# Sheet1.net
KiCad netlist of a schematic drawn in Altium Designer
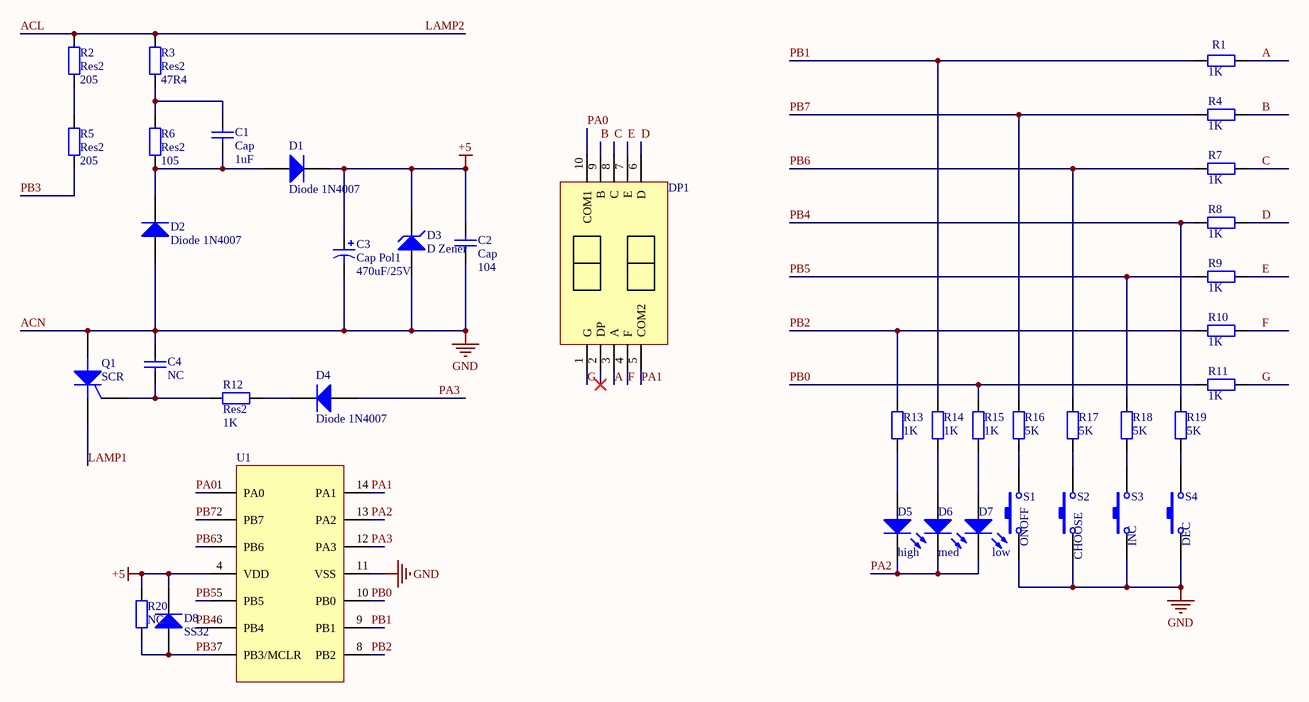
[diagram p0: Sheet1.SchDoc]

(export (version "E")
  (design (tool "Eeschema 10.0.6"))
  (components
    (comp (ref "C1")
      (value "Cap")
      (footprint "RAD-0.3")
      (description "Capacitor")
      (fields (field (name "ALTIUM_VALUE") "1uF") (field (name "PUBLISHER") "Altium Limited"))
      (libsource (lib "Miscellaneous Devices") (part "Cap"))
    )
    (comp (ref "C2")
      (value "Cap")
      (footprint "RAD-0.3")
      (description "Capacitor")
      (fields (field (name "ALTIUM_VALUE") "104") (field (name "PUBLISHER") "Altium Limited"))
      (libsource (lib "Miscellaneous Devices") (part "Cap"))
    )
    (comp (ref "C3")
      (value "Cap Pol1")
      (footprint "RB7.6-15")
      (description "Polarized Capacitor (Radial)")
      (fields (field (name "ALTIUM_VALUE") "470uF/25V") (field (name "PUBLISHER") "Altium Limited"))
      (libsource (lib "Miscellaneous Devices") (part "Cap Pol1"))
    )
    (comp (ref "C4")
      (value "NC")
      (footprint "RAD-0.3")
      (description "Capacitor")
      (fields (field (name "PUBLISHER") "Altium Limited"))
      (libsource (lib "Miscellaneous Devices") (part "Cap"))
    )
    (comp (ref "D1")
      (value "Diode 1N4007")
      (footprint "DO-41")
      (description "1 Amp General Purpose Rectifier")
      (fields (field (name "PUBLISHER") "Altium Limited"))
      (libsource (lib "Miscellaneous Devices") (part "Diode 1N4007"))
    )
    (comp (ref "D2")
      (value "Diode 1N4007")
      (footprint "DO-41")
      (description "1 Amp General Purpose Rectifier")
      (fields (field (name "PUBLISHER") "Altium Limited"))
      (libsource (lib "Miscellaneous Devices") (part "Diode 1N4007"))
    )
    (comp (ref "D3")
      (value "D Zener")
      (footprint "DIODE-0.7")
      (description "Zener Diode")
      (fields (field (name "PUBLISHER") "Altium Limited"))
      (libsource (lib "Miscellaneous Devices") (part "D Zener"))
    )
    (comp (ref "D4")
      (value "Diode 1N4007")
      (footprint "DO-41")
      (description "1 Amp General Purpose Rectifier")
      (fields (field (name "PUBLISHER") "Altium Limited"))
      (libsource (lib "Miscellaneous Devices") (part "Diode 1N4007"))
    )
    (comp (ref "D5")
      (value "high")
      (footprint "LED-0")
      (description "Typical INFRARED GaAs LED")
      (fields (field (name "PUBLISHER") "Altium Limited"))
      (libsource (lib "Miscellaneous Devices") (part "LED0"))
    )
    (comp (ref "D6")
      (value "med")
      (footprint "LED-0")
      (description "Typical INFRARED GaAs LED")
      (fields (field (name "PUBLISHER") "Altium Limited"))
      (libsource (lib "Miscellaneous Devices") (part "LED0"))
    )
    (comp (ref "D7")
      (value "low")
      (footprint "LED-0")
      (description "Typical INFRARED GaAs LED")
      (fields (field (name "PUBLISHER") "Altium Limited"))
      (libsource (lib "Miscellaneous Devices") (part "LED0"))
    )
    (comp (ref "D8")
      (value "SS32")
      (footprint "DO-41")
      (description "1 Amp General Purpose Rectifier")
      (fields (field (name "PUBLISHER") "Altium Limited"))
      (libsource (lib "Miscellaneous Devices") (part "Diode 1N4007"))
    )
    (comp (ref "DP1") (value "~") (libsource (lib "MyLib") (part "gongyinshumaguan*2")))
    (comp (ref "Q1")
      (value "SCR")
      (footprint "TO-220-AB")
      (description "Silicon Controlled Rectifier")
      (fields (field (name "PUBLISHER") "Altium Limited"))
      (libsource (lib "Miscellaneous Devices") (part "SCR"))
    )
    (comp (ref "R1")
      (value "1K")
      (footprint "AXIAL-0.4")
      (description "Resistor")
      (fields (field (name "Comment") "Res2") (field (name "PUBLISHER") "Altium Limited"))
      (libsource (lib "") (part "Res2_1"))
    )
    (comp (ref "R2")
      (value "Res2")
      (footprint "AXIAL-0.4")
      (description "Resistor")
      (fields (field (name "ALTIUM_VALUE") "205") (field (name "PUBLISHER") "Altium Limited"))
      (libsource (lib "Miscellaneous Devices") (part "Res2"))
    )
    (comp (ref "R3")
      (value "Res2")
      (footprint "AXIAL-0.4")
      (description "Resistor")
      (fields (field (name "ALTIUM_VALUE") "47R4") (field (name "PUBLISHER") "Altium Limited"))
      (libsource (lib "Miscellaneous Devices") (part "Res2"))
    )
    (comp (ref "R4")
      (value "1K")
      (footprint "AXIAL-0.4")
      (description "Resistor")
      (fields (field (name "Comment") "Res2") (field (name "PUBLISHER") "Altium Limited"))
      (libsource (lib "") (part "Res2_1"))
    )
    (comp (ref "R5")
      (value "Res2")
      (footprint "AXIAL-0.4")
      (description "Resistor")
      (fields (field (name "ALTIUM_VALUE") "205") (field (name "PUBLISHER") "Altium Limited"))
      (libsource (lib "Miscellaneous Devices") (part "Res2"))
    )
    (comp (ref "R6")
      (value "Res2")
      (footprint "AXIAL-0.4")
      (description "Resistor")
      (fields (field (name "ALTIUM_VALUE") "105") (field (name "PUBLISHER") "Altium Limited"))
      (libsource (lib "Miscellaneous Devices") (part "Res2"))
    )
    (comp (ref "R7")
      (value "1K")
      (footprint "AXIAL-0.4")
      (description "Resistor")
      (fields (field (name "Comment") "Res2") (field (name "PUBLISHER") "Altium Limited"))
      (libsource (lib "") (part "Res2_1"))
    )
    (comp (ref "R8")
      (value "1K")
      (footprint "AXIAL-0.4")
      (description "Resistor")
      (fields (field (name "Comment") "Res2") (field (name "PUBLISHER") "Altium Limited"))
      (libsource (lib "") (part "Res2_1"))
    )
    (comp (ref "R9")
      (value "1K")
      (footprint "AXIAL-0.4")
      (description "Resistor")
      (fields (field (name "Comment") "Res2") (field (name "PUBLISHER") "Altium Limited"))
      (libsource (lib "") (part "Res2_1"))
    )
    (comp (ref "R10")
      (value "1K")
      (footprint "AXIAL-0.4")
      (description "Resistor")
      (fields (field (name "Comment") "Res2") (field (name "PUBLISHER") "Altium Limited"))
      (libsource (lib "") (part "Res2_1"))
    )
    (comp (ref "R11")
      (value "1K")
      (footprint "AXIAL-0.4")
      (description "Resistor")
      (fields (field (name "Comment") "Res2") (field (name "PUBLISHER") "Altium Limited"))
      (libsource (lib "") (part "Res2_1"))
    )
    (comp (ref "R12")
      (value "Res2")
      (footprint "AXIAL-0.4")
      (description "Resistor")
      (fields (field (name "ALTIUM_VALUE") "1K") (field (name "PUBLISHER") "Altium Limited"))
      (libsource (lib "") (part "Res2_2"))
    )
    (comp (ref "R13")
      (value "1K")
      (footprint "AXIAL-0.4")
      (description "Resistor")
      (fields (field (name "Comment") "Res2") (field (name "PUBLISHER") "Altium Limited"))
      (libsource (lib "Miscellaneous Devices") (part "Res2"))
    )
    (comp (ref "R14")
      (value "1K")
      (footprint "AXIAL-0.4")
      (description "Resistor")
      (fields (field (name "Comment") "Res2") (field (name "PUBLISHER") "Altium Limited"))
      (libsource (lib "Miscellaneous Devices") (part "Res2"))
    )
    (comp (ref "R15")
      (value "1K")
      (footprint "AXIAL-0.4")
      (description "Resistor")
      (fields (field (name "Comment") "Res2") (field (name "PUBLISHER") "Altium Limited"))
      (libsource (lib "Miscellaneous Devices") (part "Res2"))
    )
    (comp (ref "R16")
      (value "5K")
      (footprint "AXIAL-0.4")
      (description "Resistor")
      (fields (field (name "Comment") "Res2") (field (name "PUBLISHER") "Altium Limited"))
      (libsource (lib "Miscellaneous Devices") (part "Res2"))
    )
    (comp (ref "R17")
      (value "5K")
      (footprint "AXIAL-0.4")
      (description "Resistor")
      (fields (field (name "Comment") "Res2") (field (name "PUBLISHER") "Altium Limited"))
      (libsource (lib "Miscellaneous Devices") (part "Res2"))
    )
    (comp (ref "R18")
      (value "5K")
      (footprint "AXIAL-0.4")
      (description "Resistor")
      (fields (field (name "Comment") "Res2") (field (name "PUBLISHER") "Altium Limited"))
      (libsource (lib "Miscellaneous Devices") (part "Res2"))
    )
    (comp (ref "R19")
      (value "5K")
      (footprint "AXIAL-0.4")
      (description "Resistor")
      (fields (field (name "Comment") "Res2") (field (name "PUBLISHER") "Altium Limited"))
      (libsource (lib "Miscellaneous Devices") (part "Res2"))
    )
    (comp (ref "R20")
      (value "NC")
      (footprint "AXIAL-0.4")
      (description "Resistor")
      (fields (field (name "Comment") "Res2") (field (name "PUBLISHER") "Altium Limited"))
      (libsource (lib "Miscellaneous Devices") (part "Res2"))
    )
    (comp (ref "S1")
      (value "ONOFF")
      (footprint "SPST-2")
      (description "Switch")
      (fields (field (name "PUBLISHER") "Altium Limited"))
      (libsource (lib "Miscellaneous Devices") (part "SW-PB"))
    )
    (comp (ref "S2")
      (value "CHOOSE")
      (footprint "SPST-2")
      (description "Switch")
      (fields (field (name "PUBLISHER") "Altium Limited"))
      (libsource (lib "Miscellaneous Devices") (part "SW-PB"))
    )
    (comp (ref "S3")
      (value "INC")
      (footprint "SPST-2")
      (description "Switch")
      (fields (field (name "PUBLISHER") "Altium Limited"))
      (libsource (lib "Miscellaneous Devices") (part "SW-PB"))
    )
    (comp (ref "S4")
      (value "DEC")
      (footprint "SPST-2")
      (description "Switch")
      (fields (field (name "PUBLISHER") "Altium Limited"))
      (libsource (lib "Miscellaneous Devices") (part "SW-PB"))
    )
    (comp (ref "U1") (value "SQ013-SOP14") (libsource (lib "MyLib") (part "SQ013-SOP14")))
  )
  (nets
    (net (code "1") (name "+5") (class "Default")
      (node (ref "C2") (pin "2") (pinfunction "2_2") (pintype "passive"))
      (node (ref "C3") (pin "1") (pinfunction "1_1") (pintype "passive"))
      (node (ref "D1") (pin "2") (pinfunction "K_2") (pintype "passive"))
      (node (ref "D3") (pin "2") (pinfunction "K_2") (pintype "passive"))
      (node (ref "D8") (pin "2") (pinfunction "K_2") (pintype "passive"))
      (node (ref "R20") (pin "2") (pinfunction "2_2") (pintype "passive"))
      (node (ref "U1") (pin "4") (pinfunction "VDD_4") (pintype "passive"))
    )
    (net (code "2") (name "/A") (class "Default")
      (node (ref "DP1") (pin "3") (pinfunction "A_3") (pintype "passive"))
      (node (ref "R1") (pin "2") (pinfunction "2_2") (pintype "passive"))
    )
    (net (code "3") (name "/ACL") (class "Default")
      (node (ref "R2") (pin "2") (pinfunction "2_2") (pintype "passive"))
      (node (ref "R3") (pin "2") (pinfunction "2_2") (pintype "passive"))
    )
    (net (code "4") (name "/B") (class "Default")
      (node (ref "DP1") (pin "9") (pinfunction "B_9") (pintype "passive"))
      (node (ref "R4") (pin "2") (pinfunction "2_2") (pintype "passive"))
    )
    (net (code "5") (name "/C") (class "Default")
      (node (ref "DP1") (pin "8") (pinfunction "C_8") (pintype "passive"))
      (node (ref "R7") (pin "2") (pinfunction "2_2") (pintype "passive"))
    )
    (net (code "6") (name "/D") (class "Default")
      (node (ref "DP1") (pin "6") (pinfunction "D_6") (pintype "passive"))
      (node (ref "R8") (pin "2") (pinfunction "2_2") (pintype "passive"))
    )
    (net (code "7") (name "/E") (class "Default")
      (node (ref "DP1") (pin "7") (pinfunction "E_7") (pintype "passive"))
      (node (ref "R9") (pin "2") (pinfunction "2_2") (pintype "passive"))
    )
    (net (code "8") (name "/F") (class "Default")
      (node (ref "DP1") (pin "4") (pinfunction "F_4") (pintype "passive"))
      (node (ref "R10") (pin "2") (pinfunction "2_2") (pintype "passive"))
    )
    (net (code "9") (name "/G") (class "Default")
      (node (ref "DP1") (pin "1") (pinfunction "G_1") (pintype "passive"))
      (node (ref "R11") (pin "2") (pinfunction "2_2") (pintype "passive"))
    )
    (net (code "10") (name "/LAMP1") (class "Default")
      (node (ref "Q1") (pin "3") (pinfunction "K_3") (pintype "passive"))
    )
    (net (code "11") (name "/PA0") (class "Default")
      (node (ref "DP1") (pin "10") (pinfunction "COM1_10") (pintype "passive"))
      (node (ref "U1") (pin "1") (pinfunction "PA0_1") (pintype "passive"))
    )
    (net (code "12") (name "/PA1") (class "Default")
      (node (ref "DP1") (pin "5") (pinfunction "COM2_5") (pintype "passive"))
      (node (ref "U1") (pin "14") (pinfunction "PA1_14") (pintype "passive"))
    )
    (net (code "13") (name "/PA2") (class "Default")
      (node (ref "D5") (pin "2") (pinfunction "K_2") (pintype "passive"))
      (node (ref "D6") (pin "2") (pinfunction "K_2") (pintype "passive"))
      (node (ref "D7") (pin "2") (pinfunction "K_2") (pintype "passive"))
      (node (ref "U1") (pin "13") (pinfunction "PA2_13") (pintype "passive"))
    )
    (net (code "14") (name "/PA3") (class "Default")
      (node (ref "D4") (pin "1") (pinfunction "A_1") (pintype "passive"))
      (node (ref "U1") (pin "12") (pinfunction "PA3_12") (pintype "passive"))
    )
    (net (code "15") (name "/PB0") (class "Default")
      (node (ref "R11") (pin "1") (pinfunction "1_1") (pintype "passive"))
      (node (ref "R15") (pin "2") (pinfunction "2_2") (pintype "passive"))
      (node (ref "U1") (pin "10") (pinfunction "PB0_10") (pintype "passive"))
    )
    (net (code "16") (name "/PB1") (class "Default")
      (node (ref "R1") (pin "1") (pinfunction "1_1") (pintype "passive"))
      (node (ref "R14") (pin "2") (pinfunction "2_2") (pintype "passive"))
      (node (ref "U1") (pin "9") (pinfunction "PB1_9") (pintype "passive"))
    )
    (net (code "17") (name "/PB2") (class "Default")
      (node (ref "R10") (pin "1") (pinfunction "1_1") (pintype "passive"))
      (node (ref "R13") (pin "2") (pinfunction "2_2") (pintype "passive"))
      (node (ref "U1") (pin "8") (pinfunction "PB2_8") (pintype "passive"))
    )
    (net (code "18") (name "/PB3") (class "Default")
      (node (ref "D8") (pin "1") (pinfunction "A_1") (pintype "passive"))
      (node (ref "R20") (pin "1") (pinfunction "1_1") (pintype "passive"))
      (node (ref "R5") (pin "1") (pinfunction "1_1") (pintype "passive"))
      (node (ref "U1") (pin "7") (pinfunction "PB3/MCLR_7") (pintype "passive"))
    )
    (net (code "19") (name "/PB4") (class "Default")
      (node (ref "R19") (pin "2") (pinfunction "2_2") (pintype "passive"))
      (node (ref "R8") (pin "1") (pinfunction "1_1") (pintype "passive"))
      (node (ref "U1") (pin "6") (pinfunction "PB4_6") (pintype "passive"))
    )
    (net (code "20") (name "/PB5") (class "Default")
      (node (ref "R18") (pin "2") (pinfunction "2_2") (pintype "passive"))
      (node (ref "R9") (pin "1") (pinfunction "1_1") (pintype "passive"))
      (node (ref "U1") (pin "5") (pinfunction "PB5_5") (pintype "passive"))
    )
    (net (code "21") (name "/PB6") (class "Default")
      (node (ref "R17") (pin "2") (pinfunction "2_2") (pintype "passive"))
      (node (ref "R7") (pin "1") (pinfunction "1_1") (pintype "passive"))
      (node (ref "U1") (pin "3") (pinfunction "PB6_3") (pintype "passive"))
    )
    (net (code "22") (name "/PB7") (class "Default")
      (node (ref "R16") (pin "2") (pinfunction "2_2") (pintype "passive"))
      (node (ref "R4") (pin "1") (pinfunction "1_1") (pintype "passive"))
      (node (ref "U1") (pin "2") (pinfunction "PB7_2") (pintype "passive"))
    )
    (net (code "23") (name "GND") (class "Default")
      (node (ref "C2") (pin "1") (pinfunction "1_1") (pintype "passive"))
      (node (ref "C3") (pin "2") (pinfunction "2_2") (pintype "passive"))
      (node (ref "C4") (pin "2") (pinfunction "2_2") (pintype "passive"))
      (node (ref "D2") (pin "1") (pinfunction "A_1") (pintype "passive"))
      (node (ref "D3") (pin "1") (pinfunction "A_1") (pintype "passive"))
      (node (ref "Q1") (pin "1") (pinfunction "A_1") (pintype "passive"))
      (node (ref "S1") (pin "1") (pinfunction "1_1") (pintype "passive"))
      (node (ref "S2") (pin "1") (pinfunction "1_1") (pintype "passive"))
      (node (ref "S3") (pin "1") (pinfunction "1_1") (pintype "passive"))
      (node (ref "S4") (pin "1") (pinfunction "1_1") (pintype "passive"))
      (node (ref "U1") (pin "11") (pinfunction "VSS_11") (pintype "passive"))
    )
    (net (code "24") (name "Net-(C1-Pad2)") (class "Default")
      (node (ref "C1") (pin "2") (pinfunction "2_2") (pintype "passive"))
      (node (ref "R3") (pin "1") (pinfunction "1_1") (pintype "passive"))
      (node (ref "R6") (pin "2") (pinfunction "2_2") (pintype "passive"))
    )
    (net (code "25") (name "Net-(D1-A)") (class "Default")
      (node (ref "C1") (pin "1") (pinfunction "1_1") (pintype "passive"))
      (node (ref "D1") (pin "1") (pinfunction "A_1") (pintype "passive"))
      (node (ref "D2") (pin "2") (pinfunction "K_2") (pintype "passive"))
      (node (ref "R6") (pin "1") (pinfunction "1_1") (pintype "passive"))
    )
    (net (code "26") (name "Net-(D4-K)") (class "Default")
      (node (ref "D4") (pin "2") (pinfunction "K_2") (pintype "passive"))
      (node (ref "R12") (pin "1") (pinfunction "1_1") (pintype "passive"))
    )
    (net (code "27") (name "Net-(D5-A)") (class "Default")
      (node (ref "D5") (pin "1") (pinfunction "A_1") (pintype "passive"))
      (node (ref "R13") (pin "1") (pinfunction "1_1") (pintype "passive"))
    )
    (net (code "28") (name "Net-(D6-A)") (class "Default")
      (node (ref "D6") (pin "1") (pinfunction "A_1") (pintype "passive"))
      (node (ref "R14") (pin "1") (pinfunction "1_1") (pintype "passive"))
    )
    (net (code "29") (name "Net-(D7-A)") (class "Default")
      (node (ref "D7") (pin "1") (pinfunction "A_1") (pintype "passive"))
      (node (ref "R15") (pin "1") (pinfunction "1_1") (pintype "passive"))
    )
    (net (code "30") (name "Net-(Q1-G)") (class "Default")
      (node (ref "C4") (pin "1") (pinfunction "1_1") (pintype "passive"))
      (node (ref "Q1") (pin "2") (pinfunction "G_2") (pintype "passive"))
      (node (ref "R12") (pin "2") (pinfunction "2_2") (pintype "passive"))
    )
    (net (code "31") (name "Net-(R2-Pad1)") (class "Default")
      (node (ref "R2") (pin "1") (pinfunction "1_1") (pintype "passive"))
      (node (ref "R5") (pin "2") (pinfunction "2_2") (pintype "passive"))
    )
    (net (code "32") (name "Net-(R16-Pad1)") (class "Default")
      (node (ref "R16") (pin "1") (pinfunction "1_1") (pintype "passive"))
      (node (ref "S1") (pin "2") (pinfunction "2_2") (pintype "passive"))
    )
    (net (code "33") (name "Net-(R17-Pad1)") (class "Default")
      (node (ref "R17") (pin "1") (pinfunction "1_1") (pintype "passive"))
      (node (ref "S2") (pin "2") (pinfunction "2_2") (pintype "passive"))
    )
    (net (code "34") (name "Net-(R18-Pad1)") (class "Default")
      (node (ref "R18") (pin "1") (pinfunction "1_1") (pintype "passive"))
      (node (ref "S3") (pin "2") (pinfunction "2_2") (pintype "passive"))
    )
    (net (code "35") (name "Net-(R19-Pad1)") (class "Default")
      (node (ref "R19") (pin "1") (pinfunction "1_1") (pintype "passive"))
      (node (ref "S4") (pin "2") (pinfunction "2_2") (pintype "passive"))
    )
    (net (code "36") (name "unconnected-(DP1-DP-Pad2)") (class "Default")
      (node (ref "DP1") (pin "2") (pinfunction "DP_2") (pintype "passive+no_connect"))
    )
  )
)
